# tuch-tara.net
KiCad netlist of a schematic drawn in Altium Designer
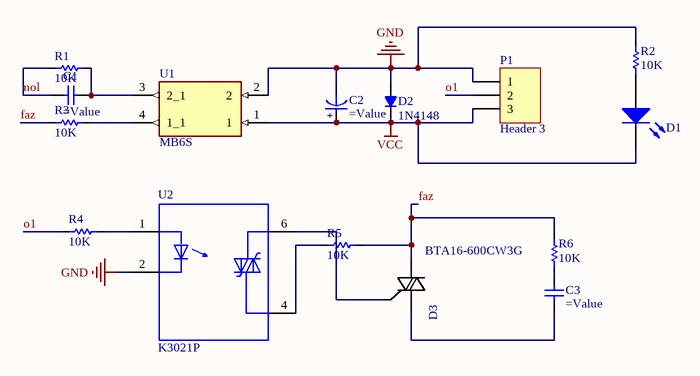
[diagram p0: tuch-tara.SchDoc]

(export (version "E")
  (design (tool "Eeschema 10.0.6"))
  (components
    (comp (ref "C1")
      (value "~")
      (footprint "CAP-30")
      (description "Capacitor")
      (libsource (lib "AltiumLib1") (part "Capacitor"))
    )
    (comp (ref "C2")
      (value "~")
      (footprint "ELEC-CAP-RAD10-20")
      (description "Electrolytic Capacitor")
      (libsource (lib "AltiumLib1") (part "Capacitor Electrolytic"))
    )
    (comp (ref "C3")
      (value "~")
      (footprint "CAP-30")
      (description "Capacitor")
      (libsource (lib "AltiumLib1") (part "Capacitor"))
    )
    (comp (ref "D1")
      (value "LED 3mm")
      (footprint "LED-3mm")
      (description "Typical LED")
      (fields (field (name "DESIGNER") "Seyed Mohsen Ghasemian") (field (name "PUBLISHER") "www.picpars.com"))
      (libsource (lib "PicPars.com_usefully_Library") (part "LED 3mm"))
    )
    (comp (ref "D2")
      (value "MODEL")
      (footprint "DO-41")
      (description "Diode")
      (fields (field (name "MODEL") "1N4148"))
      (libsource (lib "AltiumLib1") (part "Diode"))
    )
    (comp (ref "D3")
      (value "BTA16-600CW3G")
      (footprint "*TO254P1028X482X1968-3")
      (description "TRIAC Standard 600V 16A Through Hole TO-220AB")
      (fields (field (name "MF") "Littelfuse Inc."))
      (libsource (lib "BTA16-600CW3G") (part "BTA16-600CW3G"))
    )
    (comp (ref "P1")
      (value "Header 3")
      (footprint "HDR1X3")
      (description "Header, 3-Pin")
      (fields (field (name "PUBLISHER") "Altium Limited"))
      (libsource (lib "Miscellaneous Connectors") (part "Header 3"))
    )
    (comp (ref "R1")
      (value "10K")
      (footprint "Res-(1/4)")
      (description "Resistor")
      (fields (field (name "TOLERANCE") "5%") (field (name "POWER") "1/4 W"))
      (libsource (lib "AltiumLib1") (part "Resistor"))
    )
    (comp (ref "R2")
      (value "10K")
      (footprint "RES 1206 (3216X08L)")
      (description "Resistor")
      (fields (field (name "TOLERANCE") "5%") (field (name "POWER") "1/4 W"))
      (libsource (lib "AltiumLib1") (part "Resistor"))
    )
    (comp (ref "R3")
      (value "10K")
      (footprint "Res-(1/4)")
      (description "Resistor")
      (fields (field (name "TOLERANCE") "5%") (field (name "POWER") "1/4 W"))
      (libsource (lib "AltiumLib1") (part "Resistor"))
    )
    (comp (ref "R4")
      (value "10K")
      (footprint "RES 1206 (3216X08L)")
      (description "Resistor")
      (fields (field (name "TOLERANCE") "5%") (field (name "POWER") "1/4 W"))
      (libsource (lib "AltiumLib1") (part "Resistor"))
    )
    (comp (ref "R5")
      (value "10K")
      (footprint "RES 1206 (3216X08L)")
      (description "Resistor")
      (fields (field (name "TOLERANCE") "5%") (field (name "POWER") "1/4 W"))
      (libsource (lib "AltiumLib1") (part "Resistor"))
    )
    (comp (ref "R6")
      (value "10K")
      (footprint "RES 1206 (3216X08L)")
      (description "Resistor")
      (fields (field (name "TOLERANCE") "5%") (field (name "POWER") "1/4 W"))
      (libsource (lib "AltiumLib1") (part "Resistor"))
    )
    (comp (ref "U1")
      (value "MB6S")
      (footprint "SOIC245P670X270-4N")
      (description "Bridge Rectifier Single Phase Standard 600V Surface Mount 4-SOIC")
      (fields (field (name "MF") "ON Semiconductor") (field (name "DIGI-KEY_PART_NUMBER") "MB6SCT-ND"))
      (libsource (lib "MB6S") (part "MB6S"))
    )
    (comp (ref "U2")
      (value "K3021P")
      (footprint "DIP762W50P254L730H410Q6")
      (description "Optoisolator Triac Output 5300Vrms 1 Channel 6-DIP")
      (fields (field (name "MF") "Vishay Semiconductor"))
      (libsource (lib "K3021P") (part "K3021P"))
    )
  )
  (nets
    (net (code "1") (name "/faz") (class "Default")
      (node (ref "D3") (pin "2") (pinfunction "MT2_2") (pintype "passive"))
      (node (ref "R3") (pin "2") (pinfunction "2_2") (pintype "passive"))
      (node (ref "R5") (pin "2") (pinfunction "2_2") (pintype "passive"))
      (node (ref "R6") (pin "2") (pinfunction "2_2") (pintype "passive"))
    )
    (net (code "2") (name "/nol") (class "Default")
      (node (ref "C1") (pin "1") (pinfunction "+_1") (pintype "passive"))
      (node (ref "R1") (pin "2") (pinfunction "2_2") (pintype "passive"))
    )
    (net (code "3") (name "/o1") (class "Default")
      (node (ref "P1") (pin "2") (pinfunction "2_2") (pintype "passive"))
      (node (ref "R4") (pin "1") (pinfunction "1_1") (pintype "passive"))
    )
    (net (code "4") (name "GND") (class "Default")
      (node (ref "C2") (pin "1") (pinfunction "-_1") (pintype "passive"))
      (node (ref "D2") (pin "1") (pinfunction "A_1") (pintype "passive"))
      (node (ref "P1") (pin "1") (pinfunction "1_1") (pintype "passive"))
      (node (ref "R2") (pin "1") (pinfunction "1_1") (pintype "passive"))
      (node (ref "U1") (pin "2") (pinfunction "2_2") (pintype "input"))
      (node (ref "U2") (pin "2") (pinfunction "C_2") (pintype "passive"))
    )
    (net (code "5") (name "Net-(C1--)") (class "Default")
      (node (ref "C1") (pin "2") (pinfunction "-_2") (pintype "passive"))
      (node (ref "R1") (pin "1") (pinfunction "1_1") (pintype "passive"))
      (node (ref "U1") (pin "3") (pinfunction "2_1_3") (pintype "output"))
    )
    (net (code "6") (name "Net-(C3-+)") (class "Default")
      (node (ref "C3") (pin "1") (pinfunction "+_1") (pintype "passive"))
      (node (ref "D3") (pin "1") (pinfunction "MT1_1") (pintype "passive"))
    )
    (net (code "7") (name "Net-(C3--)") (class "Default")
      (node (ref "C3") (pin "2") (pinfunction "-_2") (pintype "passive"))
      (node (ref "R6") (pin "1") (pinfunction "1_1") (pintype "passive"))
    )
    (net (code "8") (name "Net-(D1-A)") (class "Default")
      (node (ref "D1") (pin "1") (pinfunction "A_1") (pintype "passive"))
      (node (ref "R2") (pin "2") (pinfunction "2_2") (pintype "passive"))
    )
    (net (code "9") (name "Net-(D3-G)") (class "Default")
      (node (ref "D3") (pin "3") (pinfunction "G_3") (pintype "passive"))
      (node (ref "U2") (pin "6") (pinfunction "MT2_6") (pintype "passive"))
    )
    (net (code "10") (name "Net-(U1-1_1)") (class "Default")
      (node (ref "R3") (pin "1") (pinfunction "1_1") (pintype "passive"))
      (node (ref "U1") (pin "4") (pinfunction "1_1_4") (pintype "output"))
    )
    (net (code "11") (name "Net-(U2-A)") (class "Default")
      (node (ref "R4") (pin "2") (pinfunction "2_2") (pintype "passive"))
      (node (ref "U2") (pin "1") (pinfunction "A_1") (pintype "passive"))
    )
    (net (code "12") (name "Net-(U2-MT1)") (class "Default")
      (node (ref "R5") (pin "1") (pinfunction "1_1") (pintype "passive"))
      (node (ref "U2") (pin "4") (pinfunction "MT1_4") (pintype "passive"))
    )
    (net (code "13") (name "VCC") (class "Default")
      (node (ref "C2") (pin "2") (pinfunction "+_2") (pintype "passive"))
      (node (ref "D1") (pin "2") (pinfunction "K_2") (pintype "passive"))
      (node (ref "D2") (pin "2") (pinfunction "K_2") (pintype "passive"))
      (node (ref "P1") (pin "3") (pinfunction "3_3") (pintype "passive"))
      (node (ref "U1") (pin "1") (pinfunction "1_1") (pintype "input"))
    )
  )
)
